# electronics.net
KiCad netlist of a schematic drawn in EAGLE
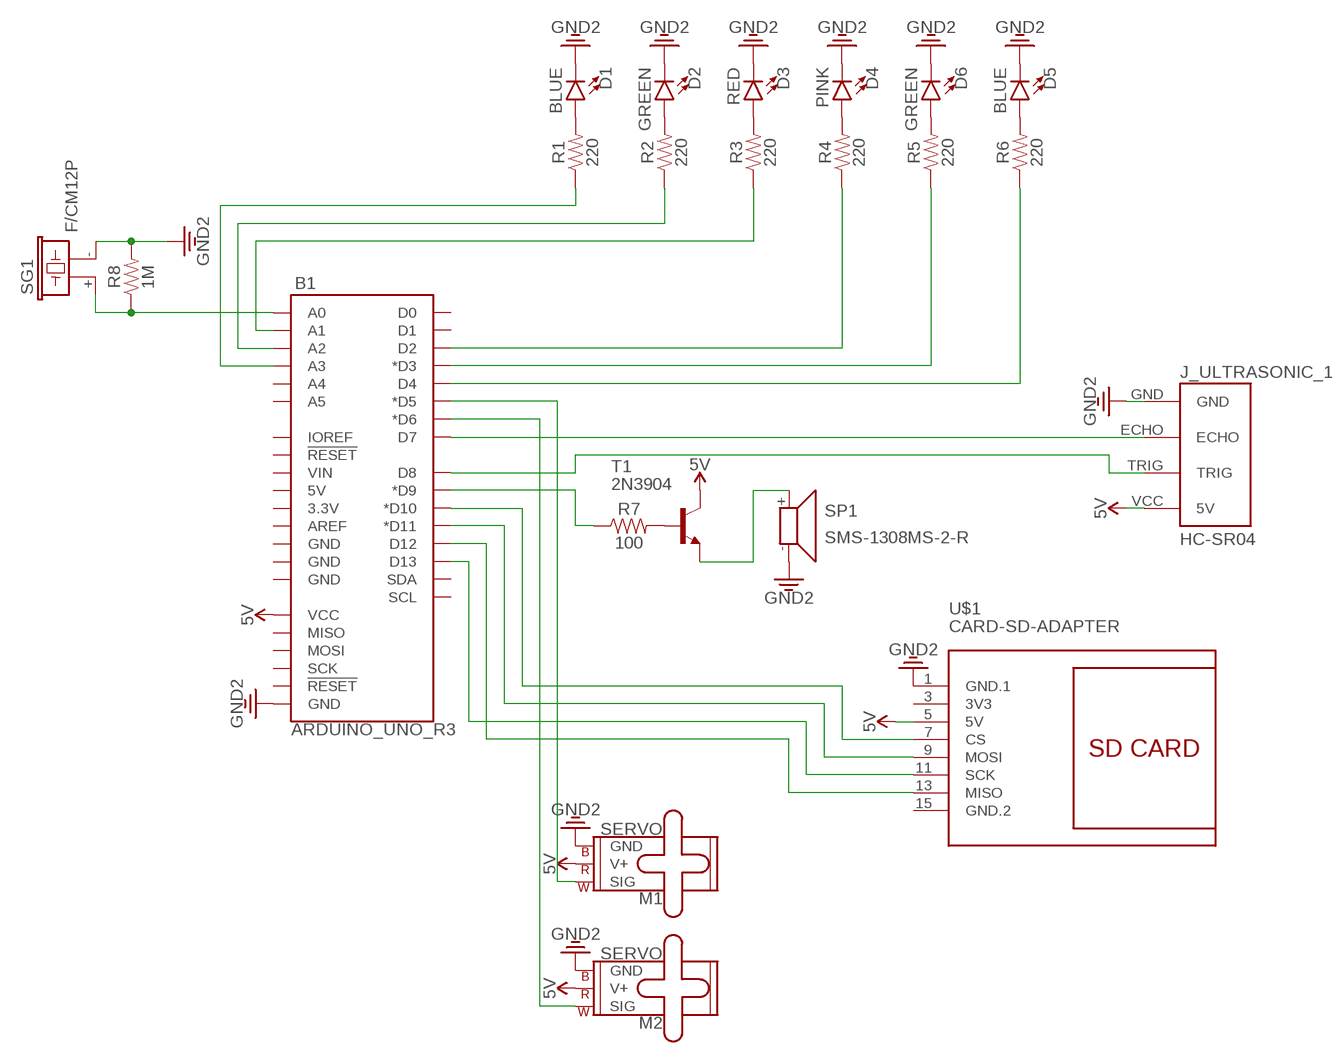
[diagram p0: schematic, sheet 1]

(export (version "E")
  (design (tool "Eeschema 10.0.6"))
  (components
    (comp (ref "B1")
      (value "ARDUINO_UNO_R3")
      (footprint "eagle-import:ARDUINO_R3")
      (libsource (lib "eagle-import") (part "ARDUINO_UNO_R3"))
    )
    (comp (ref "D1")
      (value "BLUE")
      (footprint "eagle-import:LED-0603")
      (libsource (lib "eagle-import") (part "LED-BLUE0603"))
    )
    (comp (ref "D2")
      (value "GREEN")
      (footprint "eagle-import:LED-0603")
      (libsource (lib "eagle-import") (part "LED-GREEN0603"))
    )
    (comp (ref "D3")
      (value "RED")
      (footprint "eagle-import:LED-0603")
      (libsource (lib "eagle-import") (part "LED-RED0603"))
    )
    (comp (ref "D4")
      (value "PINK")
      (footprint "eagle-import:LED-1206")
      (libsource (lib "eagle-import") (part "LED-PINK1206"))
    )
    (comp (ref "D5")
      (value "BLUE")
      (footprint "eagle-import:LED-0603")
      (libsource (lib "eagle-import") (part "LED-BLUE0603"))
    )
    (comp (ref "D6")
      (value "GREEN")
      (footprint "eagle-import:LED-0603")
      (libsource (lib "eagle-import") (part "LED-GREEN0603"))
    )
    (comp (ref "J_ULTRASONIC_1")
      (value "HC-SR04")
      (footprint "eagle-import:HC-SR04_FOOTPRINT")
      (libsource (lib "eagle-import") (part "HC-SR04"))
    )
    (comp (ref "M1")
      (value "SERVO")
      (footprint "eagle-import:1X03")
      (libsource (lib "eagle-import") (part "SERVO"))
    )
    (comp (ref "M2")
      (value "SERVO")
      (footprint "eagle-import:1X03")
      (libsource (lib "eagle-import") (part "SERVO"))
    )
    (comp (ref "R1")
      (value "220")
      (footprint "eagle-import:0603")
      (libsource (lib "eagle-import") (part "220OHM-0603-1/10W-1%"))
    )
    (comp (ref "R2")
      (value "220")
      (footprint "eagle-import:0603")
      (libsource (lib "eagle-import") (part "220OHM-0603-1/10W-1%"))
    )
    (comp (ref "R3")
      (value "220")
      (footprint "eagle-import:0603")
      (libsource (lib "eagle-import") (part "220OHM-0603-1/10W-1%"))
    )
    (comp (ref "R4")
      (value "220")
      (footprint "eagle-import:0603")
      (libsource (lib "eagle-import") (part "220OHM-0603-1/10W-1%"))
    )
    (comp (ref "R5")
      (value "220")
      (footprint "eagle-import:0603")
      (libsource (lib "eagle-import") (part "220OHM-0603-1/10W-1%"))
    )
    (comp (ref "R6")
      (value "220")
      (footprint "eagle-import:0603")
      (libsource (lib "eagle-import") (part "220OHM-0603-1/10W-1%"))
    )
    (comp (ref "R7")
      (value "100")
      (footprint "eagle-import:0603")
      (libsource (lib "eagle-import") (part "100OHM-0603-1/4W-5%"))
    )
    (comp (ref "R8")
      (value "1M")
      (footprint "eagle-import:0603")
      (libsource (lib "eagle-import") (part "1MOHM-0603-1/4W-5%"))
    )
    (comp (ref "SG1")
      (value "F/CM12P")
      (footprint "eagle-import:F_CM12P")
      (libsource (lib "eagle-import") (part "F/CM12P"))
    )
    (comp (ref "SP1")
      (value "SMS-1308MS-2-R")
      (footprint "eagle-import:SMS-1308MS-2-R")
      (libsource (lib "eagle-import") (part "SMS-1308MS-2-R"))
    )
    (comp (ref "T1")
      (value "2N3904")
      (footprint "eagle-import:TO92")
      (libsource (lib "eagle-import") (part "2N3904"))
    )
    (comp (ref "U$1")
      (value "CARD-SD-ADAPTER")
      (footprint "eagle-import:CARD-SD-ADAPTER")
      (libsource (lib "eagle-import") (part "CARD-SD-ADAPTER"))
    )
  )
  (nets
    (net (code "1") (name "/3V3") (class "Default")
      (node (ref "U$1") (pin "3") (pinfunction "3V3_3") (pintype "power_in"))
    )
    (net (code "2") (name "/GND.2") (class "Default")
      (node (ref "U$1") (pin "15") (pinfunction "GND.2_15") (pintype "power_in"))
    )
    (net (code "3") (name "5V") (class "Default")
      (node (ref "B1") (pin "VCC") (pinfunction "VCC_VCC") (pintype "bidirectional"))
      (node (ref "J_ULTRASONIC_1") (pin "VCC") (pinfunction "5V_VCC") (pintype "bidirectional"))
      (node (ref "M1") (pin "2") (pinfunction "V+_2") (pintype "bidirectional"))
      (node (ref "M2") (pin "2") (pinfunction "V+_2") (pintype "bidirectional"))
      (node (ref "T1") (pin "1") (pinfunction "C_1") (pintype "passive"))
      (node (ref "U$1") (pin "5") (pinfunction "5V_5") (pintype "power_in"))
    )
    (net (code "4") (name "GND2") (class "Default")
      (node (ref "B1") (pin "GND@1") (pinfunction "GND_GND@1") (pintype "bidirectional"))
      (node (ref "D1") (pin "C") (pinfunction "C_C") (pintype "passive"))
      (node (ref "D2") (pin "C") (pinfunction "C_C") (pintype "passive"))
      (node (ref "D3") (pin "C") (pinfunction "C_C") (pintype "passive"))
      (node (ref "D4") (pin "C") (pinfunction "C_C") (pintype "passive"))
      (node (ref "D5") (pin "C") (pinfunction "C_C") (pintype "passive"))
      (node (ref "D6") (pin "C") (pinfunction "C_C") (pintype "passive"))
      (node (ref "J_ULTRASONIC_1") (pin "GND") (pinfunction "GND_GND") (pintype "bidirectional"))
      (node (ref "M1") (pin "3") (pinfunction "GND_3") (pintype "bidirectional"))
      (node (ref "M2") (pin "3") (pinfunction "GND_3") (pintype "bidirectional"))
      (node (ref "R8") (pin "2") (pinfunction "2_2") (pintype "passive"))
      (node (ref "SG1") (pin "-") (pinfunction "2_-") (pintype "passive"))
      (node (ref "SP1") (pin "-") (pinfunction "2_-") (pintype "passive"))
      (node (ref "U$1") (pin "1") (pinfunction "GND.1_1") (pintype "power_in"))
    )
    (net (code "5") (name "Net-(B1-*D3)") (class "Default")
      (node (ref "B1") (pin "D3") (pinfunction "*D3_D3") (pintype "bidirectional"))
      (node (ref "R5") (pin "1") (pinfunction "1_1") (pintype "passive"))
    )
    (net (code "6") (name "Net-(B1-*D5)") (class "Default")
      (node (ref "B1") (pin "D5") (pinfunction "*D5_D5") (pintype "bidirectional"))
      (node (ref "M1") (pin "1") (pinfunction "SIG_1") (pintype "bidirectional"))
    )
    (net (code "7") (name "Net-(B1-*D6)") (class "Default")
      (node (ref "B1") (pin "D6") (pinfunction "*D6_D6") (pintype "bidirectional"))
      (node (ref "M2") (pin "1") (pinfunction "SIG_1") (pintype "bidirectional"))
    )
    (net (code "8") (name "Net-(B1-*D9)") (class "Default")
      (node (ref "B1") (pin "D9") (pinfunction "*D9_D9") (pintype "bidirectional"))
      (node (ref "R7") (pin "1") (pinfunction "1_1") (pintype "passive"))
    )
    (net (code "9") (name "Net-(B1-*D10)") (class "Default")
      (node (ref "B1") (pin "D10") (pinfunction "*D10_D10") (pintype "bidirectional"))
      (node (ref "U$1") (pin "7") (pinfunction "CS_7") (pintype "bidirectional"))
    )
    (net (code "10") (name "Net-(B1-*D11)") (class "Default")
      (node (ref "B1") (pin "D11") (pinfunction "*D11_D11") (pintype "bidirectional"))
      (node (ref "U$1") (pin "9") (pinfunction "MOSI_9") (pintype "bidirectional"))
    )
    (net (code "11") (name "Net-(B1-PadA1)") (class "Default")
      (node (ref "B1") (pin "A1") (pinfunction "A1_A1") (pintype "bidirectional"))
      (node (ref "R3") (pin "1") (pinfunction "1_1") (pintype "passive"))
    )
    (net (code "12") (name "Net-(B1-PadA2)") (class "Default")
      (node (ref "B1") (pin "A2") (pinfunction "A2_A2") (pintype "bidirectional"))
      (node (ref "R2") (pin "1") (pinfunction "1_1") (pintype "passive"))
    )
    (net (code "13") (name "Net-(B1-PadA3)") (class "Default")
      (node (ref "B1") (pin "A3") (pinfunction "A3_A3") (pintype "bidirectional"))
      (node (ref "R1") (pin "1") (pinfunction "1_1") (pintype "passive"))
    )
    (net (code "14") (name "Net-(B1-PadD2)") (class "Default")
      (node (ref "B1") (pin "D2") (pinfunction "D2_D2") (pintype "bidirectional"))
      (node (ref "R4") (pin "1") (pinfunction "1_1") (pintype "passive"))
    )
    (net (code "15") (name "Net-(B1-PadD4)") (class "Default")
      (node (ref "B1") (pin "D4") (pinfunction "D4_D4") (pintype "bidirectional"))
      (node (ref "R6") (pin "1") (pinfunction "1_1") (pintype "passive"))
    )
    (net (code "16") (name "Net-(B1-PadD7)") (class "Default")
      (node (ref "B1") (pin "D7") (pinfunction "D7_D7") (pintype "bidirectional"))
      (node (ref "J_ULTRASONIC_1") (pin "ECHO") (pinfunction "ECHO_ECHO") (pintype "bidirectional"))
    )
    (net (code "17") (name "Net-(B1-PadD8)") (class "Default")
      (node (ref "B1") (pin "D8") (pinfunction "D8_D8") (pintype "bidirectional"))
      (node (ref "J_ULTRASONIC_1") (pin "TRIG") (pinfunction "TRIG_TRIG") (pintype "bidirectional"))
    )
    (net (code "18") (name "Net-(D1-PadA)") (class "Default")
      (node (ref "D1") (pin "A") (pinfunction "A_A") (pintype "passive"))
      (node (ref "R1") (pin "2") (pinfunction "2_2") (pintype "passive"))
    )
    (net (code "19") (name "Net-(D2-PadA)") (class "Default")
      (node (ref "D2") (pin "A") (pinfunction "A_A") (pintype "passive"))
      (node (ref "R2") (pin "2") (pinfunction "2_2") (pintype "passive"))
    )
    (net (code "20") (name "Net-(D3-PadA)") (class "Default")
      (node (ref "D3") (pin "A") (pinfunction "A_A") (pintype "passive"))
      (node (ref "R3") (pin "2") (pinfunction "2_2") (pintype "passive"))
    )
    (net (code "21") (name "Net-(D4-PadA)") (class "Default")
      (node (ref "D4") (pin "A") (pinfunction "A_A") (pintype "passive"))
      (node (ref "R4") (pin "2") (pinfunction "2_2") (pintype "passive"))
    )
    (net (code "22") (name "Net-(D5-PadA)") (class "Default")
      (node (ref "D5") (pin "A") (pinfunction "A_A") (pintype "passive"))
      (node (ref "R6") (pin "2") (pinfunction "2_2") (pintype "passive"))
    )
    (net (code "23") (name "Net-(D6-PadA)") (class "Default")
      (node (ref "D6") (pin "A") (pinfunction "A_A") (pintype "passive"))
      (node (ref "R5") (pin "2") (pinfunction "2_2") (pintype "passive"))
    )
    (net (code "24") (name "Net-(SG1-1)") (class "Default")
      (node (ref "B1") (pin "A0") (pinfunction "A0_A0") (pintype "bidirectional"))
      (node (ref "R8") (pin "1") (pinfunction "1_1") (pintype "passive"))
      (node (ref "SG1") (pin "+") (pinfunction "1_+") (pintype "passive"))
    )
    (net (code "25") (name "Net-(SP1-1)") (class "Default")
      (node (ref "SP1") (pin "+") (pinfunction "1_+") (pintype "passive"))
      (node (ref "T1") (pin "3") (pinfunction "E_3") (pintype "passive"))
    )
    (net (code "26") (name "Net-(T1-B)") (class "Default")
      (node (ref "R7") (pin "2") (pinfunction "2_2") (pintype "passive"))
      (node (ref "T1") (pin "2") (pinfunction "B_2") (pintype "passive"))
    )
    (net (code "27") (name "Net-(U$1-MISO)") (class "Default")
      (node (ref "B1") (pin "D12") (pinfunction "D12_D12") (pintype "bidirectional"))
      (node (ref "U$1") (pin "13") (pinfunction "MISO_13") (pintype "bidirectional"))
    )
    (net (code "28") (name "Net-(U$1-SCK)") (class "Default")
      (node (ref "B1") (pin "D13") (pinfunction "D13_D13") (pintype "bidirectional"))
      (node (ref "U$1") (pin "11") (pinfunction "SCK_11") (pintype "bidirectional"))
    )
    (net (code "29") (name "unconnected-(B1-GND-PadGND@2)") (class "Default")
      (node (ref "B1") (pin "GND@2") (pinfunction "GND_GND@2") (pintype "bidirectional"))
    )
    (net (code "30") (name "unconnected-(B1-GND-PadGND@3)") (class "Default")
      (node (ref "B1") (pin "GND@3") (pinfunction "GND_GND@3") (pintype "bidirectional"))
    )
    (net (code "31") (name "unconnected-(B1-GND-PadGND@4)") (class "Default")
      (node (ref "B1") (pin "GND@4") (pinfunction "GND_GND@4") (pintype "bidirectional"))
    )
    (net (code "32") (name "unconnected-(B1-Pad3.3V)") (class "Default")
      (node (ref "B1") (pin "3.3V") (pinfunction "3.3V_3.3V") (pintype "bidirectional"))
    )
    (net (code "33") (name "unconnected-(B1-Pad5V)") (class "Default")
      (node (ref "B1") (pin "5V") (pinfunction "5V_5V") (pintype "bidirectional"))
    )
    (net (code "34") (name "unconnected-(B1-PadA4)") (class "Default")
      (node (ref "B1") (pin "A4") (pinfunction "A4_A4") (pintype "bidirectional"))
    )
    (net (code "35") (name "unconnected-(B1-PadA5)") (class "Default")
      (node (ref "B1") (pin "A5") (pinfunction "A5_A5") (pintype "bidirectional"))
    )
    (net (code "36") (name "unconnected-(B1-PadAREF)") (class "Default")
      (node (ref "B1") (pin "AREF") (pinfunction "AREF_AREF") (pintype "bidirectional"))
    )
    (net (code "37") (name "unconnected-(B1-PadD0)") (class "Default")
      (node (ref "B1") (pin "D0") (pinfunction "D0_D0") (pintype "bidirectional"))
    )
    (net (code "38") (name "unconnected-(B1-PadD1)") (class "Default")
      (node (ref "B1") (pin "D1") (pinfunction "D1_D1") (pintype "bidirectional"))
    )
    (net (code "39") (name "unconnected-(B1-PadIOREF)") (class "Default")
      (node (ref "B1") (pin "IOREF") (pinfunction "IOREF_IOREF") (pintype "bidirectional"))
    )
    (net (code "40") (name "unconnected-(B1-PadMISO)") (class "Default")
      (node (ref "B1") (pin "MISO") (pinfunction "MISO_MISO") (pintype "bidirectional"))
    )
    (net (code "41") (name "unconnected-(B1-PadMOSI)") (class "Default")
      (node (ref "B1") (pin "MOSI") (pinfunction "MOSI_MOSI") (pintype "bidirectional"))
    )
    (net (code "42") (name "unconnected-(B1-PadSCK)") (class "Default")
      (node (ref "B1") (pin "SCK") (pinfunction "SCK_SCK") (pintype "bidirectional"))
    )
    (net (code "43") (name "unconnected-(B1-PadSCL)") (class "Default")
      (node (ref "B1") (pin "SCL") (pinfunction "SCL_SCL") (pintype "bidirectional"))
    )
    (net (code "44") (name "unconnected-(B1-PadSDA)") (class "Default")
      (node (ref "B1") (pin "SDA") (pinfunction "SDA_SDA") (pintype "bidirectional"))
    )
    (net (code "45") (name "unconnected-(B1-PadVIN)") (class "Default")
      (node (ref "B1") (pin "VIN") (pinfunction "VIN_VIN") (pintype "bidirectional"))
    )
    (net (code "46") (name "unconnected-(B1-~{RESET}-PadRESET@1)") (class "Default")
      (node (ref "B1") (pin "RESET@1") (pinfunction "~{RESET}_RESET@1") (pintype "bidirectional"))
    )
    (net (code "47") (name "unconnected-(B1-~{RESET}-PadRESET@2)") (class "Default")
      (node (ref "B1") (pin "RESET@2") (pinfunction "~{RESET}_RESET@2") (pintype "bidirectional"))
    )
  )
)
